# freq-meter.net
KiCad netlist of a schematic drawn in Altium Designer
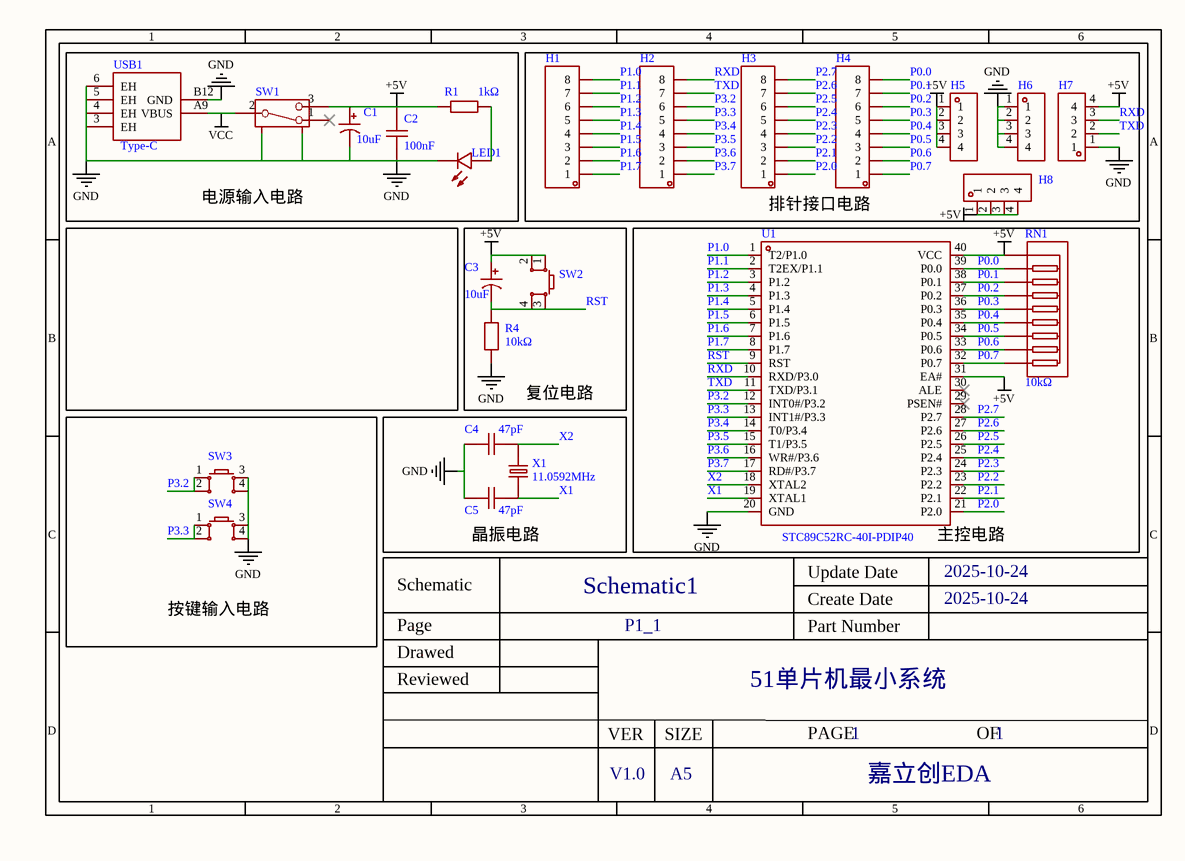
[diagram p0: freq-meter.schdoc]

(export (version "E")
  (design (tool "Eeschema 10.0.6"))
  (components
    (comp (ref "C1")
      (value "10uF")
      (footprint "CAP-TH_BD5.0-P2.00-D0.8-FD")
      (fields
        (field (name "MANUFACTURER") "CX(承兴)")
        (field (name "MANUFACTURER PART") "KM106M050D11RR0VH2FP0")
        (field (name "ALTIUM_VALUE") "10uF")
        (field (name "TOLERANCE") "±20%")
      )
      (libsource (lib "altium-import") (part "root_3_KM106M050D11RR0VH2FP0_"))
    )
    (comp (ref "C2")
      (value "100nF")
      (footprint "CAP-TH_L8.5-W5.0-P5.00-D1.2")
      (fields
        (field (name "MANUFACTURER") "FH(风华)")
        (field (name "MANUFACTURER PART") "CT4-0805B104K500F3")
        (field (name "ALTIUM_VALUE") "100nF")
        (field (name "TOLERANCE") "±10%")
      )
      (libsource (lib "altium-import") (part "root_1_CT4-0805B104K500F3_"))
    )
    (comp (ref "C3")
      (value "10uF")
      (footprint "CAP-TH_BD5.0-P2.00-D0.8-FD")
      (fields
        (field (name "MANUFACTURER") "CX(承兴)")
        (field (name "MANUFACTURER PART") "KM106M050D11RR0VH2FP0")
        (field (name "ALTIUM_VALUE") "10uF")
        (field (name "TOLERANCE") "±20%")
      )
      (libsource (lib "altium-import") (part "root_3_KM106M050D11RR0VH2FP0_"))
    )
    (comp (ref "C4")
      (value "47pF")
      (footprint "CAP-TH_L4.5-W3.0-P5.00-D1.2")
      (fields
        (field (name "MANUFACTURER") "Dersonic(德尔创)")
        (field (name "MANUFACTURER PART") "CC1H470JC74DCH4B10MN")
        (field (name "ALTIUM_VALUE") "47pF")
        (field (name "TOLERANCE") "±5%")
      )
      (libsource (lib "altium-import") (part "root_0_CC1H470JC74DCH4B10MN_"))
    )
    (comp (ref "C5")
      (value "47pF")
      (footprint "CAP-TH_L4.5-W3.0-P5.00-D1.2")
      (fields
        (field (name "MANUFACTURER") "Dersonic(德尔创)")
        (field (name "MANUFACTURER PART") "CC1H470JC74DCH4B10MN")
        (field (name "ALTIUM_VALUE") "47pF")
        (field (name "TOLERANCE") "±5%")
      )
      (libsource (lib "altium-import") (part "root_0_CC1H470JC74DCH4B10MN_"))
    )
    (comp (ref "H1")
      (value "~")
      (footprint "HDR-TH_8P-P2.54-V-M")
      (libsource (lib "altium-import") (part "root_2_HDR-M_2.54_1x8P_"))
    )
    (comp (ref "H2")
      (value "~")
      (footprint "HDR-TH_8P-P2.54-V-M")
      (libsource (lib "altium-import") (part "root_2_HDR-M_2.54_1x8P_"))
    )
    (comp (ref "H3")
      (value "~")
      (footprint "HDR-TH_8P-P2.54-V-M")
      (libsource (lib "altium-import") (part "root_2_HDR-M_2.54_1x8P_"))
    )
    (comp (ref "H4")
      (value "~")
      (footprint "HDR-TH_8P-P2.54-V-M")
      (libsource (lib "altium-import") (part "root_2_HDR-M_2.54_1x8P_"))
    )
    (comp (ref "H5")
      (value "~")
      (footprint "HDR-TH_4P-P2.54-V-M")
      (libsource (lib "altium-import") (part "root_0_HDR-M_2.54_1x4P_"))
    )
    (comp (ref "H6")
      (value "~")
      (footprint "HDR-TH_4P-P2.54-V-M")
      (libsource (lib "altium-import") (part "root_0_HDR-M_2.54_1x4P_"))
    )
    (comp (ref "H7")
      (value "~")
      (footprint "HDR-TH_4P-P2.54-V-M")
      (libsource (lib "altium-import") (part "root_2_HDR-M_2.54_1x4P_"))
    )
    (comp (ref "H8")
      (value "~")
      (footprint "HDR-TH_4P-P2.54-V-M")
      (libsource (lib "altium-import") (part "root_1_HDR-M_2.54_1x4P_"))
    )
    (comp (ref "LED1")
      (value "204-10SURD/S530-A3-L")
      (footprint "LED-TH_BD3.0-P2.54-FD")
      (fields (field (name "MANUFACTURER") "EVERLIGHT(亿光)"))
      (libsource (lib "altium-import") (part "root_2_204-10SURD/S530-A3-L_"))
    )
    (comp (ref "R1")
      (value "1kΩ")
      (footprint "RES-TH_BD2.5-L6.5-P10.50-D0.6")
      (fields
        (field (name "MANUFACTURER") "UNI-ROYAL(厚声)")
        (field (name "MANUFACTURER PART") "MFR0W4F1001A50")
        (field (name "ALTIUM_VALUE") "1kΩ")
        (field (name "TOLERANCE") "±1%")
      )
      (libsource (lib "altium-import") (part "root_0_MFR0W4F1001A50_"))
    )
    (comp (ref "R4")
      (value "10kΩ")
      (footprint "RES-TH_BD2.4-L6.3-P10.30-D0.6")
      (fields
        (field (name "MANUFACTURER") "Tyohm(幸亚电阻)")
        (field (name "MANUFACTURER PART") "RN1/4W10KFT/BA1")
        (field (name "ALTIUM_VALUE") "10kΩ")
        (field (name "TOLERANCE") "±1%")
      )
      (libsource (lib "altium-import") (part "root_1_RN1/4W10KFT/BA1_"))
    )
    (comp (ref "RN1")
      (value "10kΩ")
      (footprint "RES-ARRAY-TH_9P-P2.54-D1.0")
      (fields
        (field (name "MANUFACTURER") "FH(风华)")
        (field (name "MANUFACTURER PART") "A09-103JP")
        (field (name "ALTIUM_VALUE") "10kΩ")
        (field (name "TOLERANCE") "±5%")
      )
      (libsource (lib "altium-import") (part "root_0_A09-103JP_"))
    )
    (comp (ref "SW1")
      (value "SS-12D02-VG4")
      (footprint "SW-TH_SS-12D02-VG4")
      (fields (field (name "MANUFACTURER") "韩国韩荣"))
      (libsource (lib "altium-import") (part "root_0_SS-12D02-VG4_C136719_"))
    )
    (comp (ref "SW2")
      (value "~")
      (footprint "SW-TH_4P-L6.0-W6.0-P4.50-LS6.5")
      (libsource (lib "altium-import") (part "root_3_Key_TH_6x6x6_"))
    )
    (comp (ref "SW3")
      (value "~")
      (footprint "SW-TH_4P-L6.0-W6.0-P4.50-LS6.5")
      (libsource (lib "altium-import") (part "root_0_Key_TH_6x6x6_"))
    )
    (comp (ref "SW4")
      (value "~")
      (footprint "SW-TH_4P-L6.0-W6.0-P4.50-LS6.5")
      (libsource (lib "altium-import") (part "root_0_Key_TH_6x6x6_"))
    )
    (comp (ref "U1")
      (value "STC89C52RC-40I-PDIP40")
      (footprint "DIP-40_L52.0-W13.7-P2.54-LS15.2-BL")
      (fields
        (field (name "MANUFACTURER") "STC(宏晶)")
        (field (name "MANUFACTURER PART") "STC89C52RC-40I-PDIP40")
      )
      (libsource (lib "altium-import") (part "root_0_STC89C52RC-40I-PDIP40_"))
    )
    (comp (ref "USB1")
      (value "TYPE-C-31-M-33")
      (footprint "USB-C-TH_TYPE-C-31-M-33")
      (fields (field (name "MANUFACTURER") "韩国韩荣") (field (name "CONNECTOR TYPE") "Type-C"))
      (libsource (lib "altium-import") (part "root_2_TYPE-C-31-M-33_"))
    )
    (comp (ref "X1")
      (value "11.0592MHz")
      (footprint "HC-49US_L11.5-W4.5-P4.88")
      (fields
        (field (name "MANUFACTURER") "TAE(雅晶鑫)")
        (field (name "MANUFACTURER PART") "TAXD11.0592M2GLFBET2T")
        (field (name "ALTIUM_VALUE") "11.0592MHz")
      )
      (libsource (lib "altium-import") (part "root_1_TAXD11.0592M2GLFBET2T_"))
    )
  )
  (nets
    (net (code "1") (name "+5V") (class "Default")
      (node (ref "C1") (pin "1") (pinfunction "1_1") (pintype "passive"))
      (node (ref "C2") (pin "2") (pinfunction "2_2") (pintype "passive"))
      (node (ref "C3") (pin "1") (pinfunction "1_1") (pintype "passive"))
      (node (ref "H5") (pin "1") (pinfunction "1_1") (pintype "passive"))
      (node (ref "H5") (pin "2") (pinfunction "2_2") (pintype "passive"))
      (node (ref "H5") (pin "3") (pinfunction "3_3") (pintype "passive"))
      (node (ref "H5") (pin "4") (pinfunction "4_4") (pintype "passive"))
      (node (ref "H7") (pin "4") (pinfunction "4_4") (pintype "passive"))
      (node (ref "H8") (pin "1") (pinfunction "1_1") (pintype "passive"))
      (node (ref "H8") (pin "2") (pinfunction "2_2") (pintype "passive"))
      (node (ref "H8") (pin "3") (pinfunction "3_3") (pintype "passive"))
      (node (ref "H8") (pin "4") (pinfunction "4_4") (pintype "passive"))
      (node (ref "R1") (pin "1") (pinfunction "1_1") (pintype "passive"))
      (node (ref "RN1") (pin "1") (pinfunction "1_1") (pintype "passive"))
      (node (ref "SW1") (pin "3") (pinfunction "3_3") (pintype "passive"))
      (node (ref "SW2") (pin "1") (pinfunction "1_1") (pintype "passive"))
      (node (ref "SW2") (pin "2") (pinfunction "2_2") (pintype "passive"))
      (node (ref "U1") (pin "31") (pinfunction "EA#_31") (pintype "passive"))
      (node (ref "U1") (pin "40") (pinfunction "VCC_40") (pintype "passive"))
    )
    (net (code "2") (name "/P0.0") (class "Default")
      (node (ref "H4") (pin "8") (pinfunction "8_8") (pintype "passive"))
      (node (ref "RN1") (pin "2") (pinfunction "2_2") (pintype "passive"))
      (node (ref "U1") (pin "39") (pinfunction "P0.0_39") (pintype "passive"))
    )
    (net (code "3") (name "/P0.1") (class "Default")
      (node (ref "H4") (pin "7") (pinfunction "7_7") (pintype "passive"))
      (node (ref "RN1") (pin "3") (pinfunction "3_3") (pintype "passive"))
      (node (ref "U1") (pin "38") (pinfunction "P0.1_38") (pintype "passive"))
    )
    (net (code "4") (name "/P0.2") (class "Default")
      (node (ref "H4") (pin "6") (pinfunction "6_6") (pintype "passive"))
      (node (ref "RN1") (pin "4") (pinfunction "4_4") (pintype "passive"))
      (node (ref "U1") (pin "37") (pinfunction "P0.2_37") (pintype "passive"))
    )
    (net (code "5") (name "/P0.3") (class "Default")
      (node (ref "H4") (pin "5") (pinfunction "5_5") (pintype "passive"))
      (node (ref "RN1") (pin "5") (pinfunction "5_5") (pintype "passive"))
      (node (ref "U1") (pin "36") (pinfunction "P0.3_36") (pintype "passive"))
    )
    (net (code "6") (name "/P0.4") (class "Default")
      (node (ref "H4") (pin "4") (pinfunction "4_4") (pintype "passive"))
      (node (ref "RN1") (pin "6") (pinfunction "6_6") (pintype "passive"))
      (node (ref "U1") (pin "35") (pinfunction "P0.4_35") (pintype "passive"))
    )
    (net (code "7") (name "/P0.5") (class "Default")
      (node (ref "H4") (pin "3") (pinfunction "3_3") (pintype "passive"))
      (node (ref "RN1") (pin "7") (pinfunction "7_7") (pintype "passive"))
      (node (ref "U1") (pin "34") (pinfunction "P0.5_34") (pintype "passive"))
    )
    (net (code "8") (name "/P0.6") (class "Default")
      (node (ref "H4") (pin "2") (pinfunction "2_2") (pintype "passive"))
      (node (ref "RN1") (pin "8") (pinfunction "8_8") (pintype "passive"))
      (node (ref "U1") (pin "33") (pinfunction "P0.6_33") (pintype "passive"))
    )
    (net (code "9") (name "/P0.7") (class "Default")
      (node (ref "H4") (pin "1") (pinfunction "1_1") (pintype "passive"))
      (node (ref "RN1") (pin "9") (pinfunction "9_9") (pintype "passive"))
      (node (ref "U1") (pin "32") (pinfunction "P0.7_32") (pintype "passive"))
    )
    (net (code "10") (name "/P1.0") (class "Default")
      (node (ref "H1") (pin "8") (pinfunction "8_8") (pintype "passive"))
      (node (ref "U1") (pin "1") (pinfunction "T2/P1.0_1") (pintype "passive"))
    )
    (net (code "11") (name "/P1.1") (class "Default")
      (node (ref "H1") (pin "7") (pinfunction "7_7") (pintype "passive"))
      (node (ref "U1") (pin "2") (pinfunction "T2EX/P1.1_2") (pintype "passive"))
    )
    (net (code "12") (name "/P1.2") (class "Default")
      (node (ref "H1") (pin "6") (pinfunction "6_6") (pintype "passive"))
      (node (ref "U1") (pin "3") (pinfunction "P1.2_3") (pintype "passive"))
    )
    (net (code "13") (name "/P1.3") (class "Default")
      (node (ref "H1") (pin "5") (pinfunction "5_5") (pintype "passive"))
      (node (ref "U1") (pin "4") (pinfunction "P1.3_4") (pintype "passive"))
    )
    (net (code "14") (name "/P1.4") (class "Default")
      (node (ref "H1") (pin "4") (pinfunction "4_4") (pintype "passive"))
      (node (ref "U1") (pin "5") (pinfunction "P1.4_5") (pintype "passive"))
    )
    (net (code "15") (name "/P1.5") (class "Default")
      (node (ref "H1") (pin "3") (pinfunction "3_3") (pintype "passive"))
      (node (ref "U1") (pin "6") (pinfunction "P1.5_6") (pintype "passive"))
    )
    (net (code "16") (name "/P1.6") (class "Default")
      (node (ref "H1") (pin "2") (pinfunction "2_2") (pintype "passive"))
      (node (ref "U1") (pin "7") (pinfunction "P1.6_7") (pintype "passive"))
    )
    (net (code "17") (name "/P1.7") (class "Default")
      (node (ref "H1") (pin "1") (pinfunction "1_1") (pintype "passive"))
      (node (ref "U1") (pin "8") (pinfunction "P1.7_8") (pintype "passive"))
    )
    (net (code "18") (name "/P2.0") (class "Default")
      (node (ref "H3") (pin "1") (pinfunction "1_1") (pintype "passive"))
      (node (ref "U1") (pin "21") (pinfunction "P2.0_21") (pintype "passive"))
    )
    (net (code "19") (name "/P2.1") (class "Default")
      (node (ref "H3") (pin "2") (pinfunction "2_2") (pintype "passive"))
      (node (ref "U1") (pin "22") (pinfunction "P2.1_22") (pintype "passive"))
    )
    (net (code "20") (name "/P2.2") (class "Default")
      (node (ref "H3") (pin "3") (pinfunction "3_3") (pintype "passive"))
      (node (ref "U1") (pin "23") (pinfunction "P2.2_23") (pintype "passive"))
    )
    (net (code "21") (name "/P2.3") (class "Default")
      (node (ref "H3") (pin "4") (pinfunction "4_4") (pintype "passive"))
      (node (ref "U1") (pin "24") (pinfunction "P2.3_24") (pintype "passive"))
    )
    (net (code "22") (name "/P2.4") (class "Default")
      (node (ref "H3") (pin "5") (pinfunction "5_5") (pintype "passive"))
      (node (ref "U1") (pin "25") (pinfunction "P2.4_25") (pintype "passive"))
    )
    (net (code "23") (name "/P2.5") (class "Default")
      (node (ref "H3") (pin "6") (pinfunction "6_6") (pintype "passive"))
      (node (ref "U1") (pin "26") (pinfunction "P2.5_26") (pintype "passive"))
    )
    (net (code "24") (name "/P2.6") (class "Default")
      (node (ref "H3") (pin "7") (pinfunction "7_7") (pintype "passive"))
      (node (ref "U1") (pin "27") (pinfunction "P2.6_27") (pintype "passive"))
    )
    (net (code "25") (name "/P2.7") (class "Default")
      (node (ref "H3") (pin "8") (pinfunction "8_8") (pintype "passive"))
      (node (ref "U1") (pin "28") (pinfunction "P2.7_28") (pintype "passive"))
    )
    (net (code "26") (name "/P3.2") (class "Default")
      (node (ref "H2") (pin "6") (pinfunction "6_6") (pintype "passive"))
      (node (ref "SW3") (pin "1") (pinfunction "1_1") (pintype "passive"))
      (node (ref "SW3") (pin "2") (pinfunction "2_2") (pintype "passive"))
      (node (ref "U1") (pin "12") (pinfunction "INT0#/P3.2_12") (pintype "passive"))
    )
    (net (code "27") (name "/P3.3") (class "Default")
      (node (ref "H2") (pin "5") (pinfunction "5_5") (pintype "passive"))
      (node (ref "SW4") (pin "1") (pinfunction "1_1") (pintype "passive"))
      (node (ref "SW4") (pin "2") (pinfunction "2_2") (pintype "passive"))
      (node (ref "U1") (pin "13") (pinfunction "INT1#/P3.3_13") (pintype "passive"))
    )
    (net (code "28") (name "/P3.4") (class "Default")
      (node (ref "H2") (pin "4") (pinfunction "4_4") (pintype "passive"))
      (node (ref "U1") (pin "14") (pinfunction "T0/P3.4_14") (pintype "passive"))
    )
    (net (code "29") (name "/P3.5") (class "Default")
      (node (ref "H2") (pin "3") (pinfunction "3_3") (pintype "passive"))
      (node (ref "U1") (pin "15") (pinfunction "T1/P3.5_15") (pintype "passive"))
    )
    (net (code "30") (name "/P3.6") (class "Default")
      (node (ref "H2") (pin "2") (pinfunction "2_2") (pintype "passive"))
      (node (ref "U1") (pin "16") (pinfunction "WR#/P3.6_16") (pintype "passive"))
    )
    (net (code "31") (name "/P3.7") (class "Default")
      (node (ref "H2") (pin "1") (pinfunction "1_1") (pintype "passive"))
      (node (ref "U1") (pin "17") (pinfunction "RD#/P3.7_17") (pintype "passive"))
    )
    (net (code "32") (name "/RST") (class "Default")
      (node (ref "C3") (pin "2") (pinfunction "2_2") (pintype "passive"))
      (node (ref "R4") (pin "2") (pinfunction "2_2") (pintype "passive"))
      (node (ref "SW2") (pin "3") (pinfunction "3_3") (pintype "passive"))
      (node (ref "SW2") (pin "4") (pinfunction "4_4") (pintype "passive"))
      (node (ref "U1") (pin "9") (pinfunction "RST_9") (pintype "passive"))
    )
    (net (code "33") (name "/RXD") (class "Default")
      (node (ref "H2") (pin "8") (pinfunction "8_8") (pintype "passive"))
      (node (ref "H7") (pin "3") (pinfunction "3_3") (pintype "passive"))
      (node (ref "U1") (pin "10") (pinfunction "RXD/P3.0_10") (pintype "passive"))
    )
    (net (code "34") (name "/TXD") (class "Default")
      (node (ref "H2") (pin "7") (pinfunction "7_7") (pintype "passive"))
      (node (ref "H7") (pin "2") (pinfunction "2_2") (pintype "passive"))
      (node (ref "U1") (pin "11") (pinfunction "TXD/P3.1_11") (pintype "passive"))
    )
    (net (code "35") (name "/X1") (class "Default")
      (node (ref "C5") (pin "2") (pinfunction "2_2") (pintype "passive"))
      (node (ref "U1") (pin "19") (pinfunction "XTAL1_19") (pintype "passive"))
      (node (ref "X1") (pin "1") (pinfunction "1_1") (pintype "passive"))
    )
    (net (code "36") (name "/X2") (class "Default")
      (node (ref "C4") (pin "2") (pinfunction "2_2") (pintype "passive"))
      (node (ref "U1") (pin "18") (pinfunction "XTAL2_18") (pintype "passive"))
      (node (ref "X1") (pin "2") (pinfunction "2_2") (pintype "passive"))
    )
    (net (code "37") (name "GND") (class "Default")
      (node (ref "C1") (pin "2") (pinfunction "2_2") (pintype "passive"))
      (node (ref "C2") (pin "1") (pinfunction "1_1") (pintype "passive"))
      (node (ref "C4") (pin "1") (pinfunction "1_1") (pintype "passive"))
      (node (ref "C5") (pin "1") (pinfunction "1_1") (pintype "passive"))
      (node (ref "H6") (pin "1") (pinfunction "1_1") (pintype "passive"))
      (node (ref "H6") (pin "2") (pinfunction "2_2") (pintype "passive"))
      (node (ref "H6") (pin "3") (pinfunction "3_3") (pintype "passive"))
      (node (ref "H6") (pin "4") (pinfunction "4_4") (pintype "passive"))
      (node (ref "H7") (pin "1") (pinfunction "1_1") (pintype "passive"))
      (node (ref "LED1") (pin "2") (pinfunction "K_2") (pintype "passive"))
      (node (ref "R4") (pin "1") (pinfunction "1_1") (pintype "passive"))
      (node (ref "SW1") (pin "4") (pinfunction "4_4") (pintype "passive"))
      (node (ref "SW1") (pin "5") (pinfunction "5_5") (pintype "passive"))
      (node (ref "SW3") (pin "3") (pinfunction "3_3") (pintype "passive"))
      (node (ref "SW3") (pin "4") (pinfunction "4_4") (pintype "passive"))
      (node (ref "SW4") (pin "3") (pinfunction "3_3") (pintype "passive"))
      (node (ref "SW4") (pin "4") (pinfunction "4_4") (pintype "passive"))
      (node (ref "U1") (pin "20") (pinfunction "GND_20") (pintype "passive"))
      (node (ref "USB1") (pin "3") (pinfunction "EH_3") (pintype "passive"))
      (node (ref "USB1") (pin "4") (pinfunction "EH_4") (pintype "passive"))
      (node (ref "USB1") (pin "5") (pinfunction "EH_5") (pintype "passive"))
      (node (ref "USB1") (pin "6") (pinfunction "EH_6") (pintype "passive"))
      (node (ref "USB1") (pin "B12") (pinfunction "GND_B12") (pintype "passive"))
    )
    (net (code "38") (name "Net-(LED1-A)") (class "Default")
      (node (ref "LED1") (pin "1") (pinfunction "A_1") (pintype "passive"))
      (node (ref "R1") (pin "2") (pinfunction "2_2") (pintype "passive"))
    )
    (net (code "39") (name "VCC") (class "Default")
      (node (ref "SW1") (pin "2") (pinfunction "2_2") (pintype "passive"))
      (node (ref "USB1") (pin "A9") (pinfunction "VBUS_A9") (pintype "passive"))
    )
    (net (code "40") (name "unconnected-(SW1-Pad1)") (class "Default")
      (node (ref "SW1") (pin "1") (pinfunction "1_1") (pintype "passive+no_connect"))
    )
    (net (code "41") (name "unconnected-(U1-ALE-Pad30)") (class "Default")
      (node (ref "U1") (pin "30") (pinfunction "ALE_30") (pintype "passive+no_connect"))
    )
    (net (code "42") (name "unconnected-(U1-PSEN#-Pad29)") (class "Default")
      (node (ref "U1") (pin "29") (pinfunction "PSEN#_29") (pintype "passive+no_connect"))
    )
  )
)
